# xmega32devboard.net
KiCad netlist of a schematic drawn in EAGLE
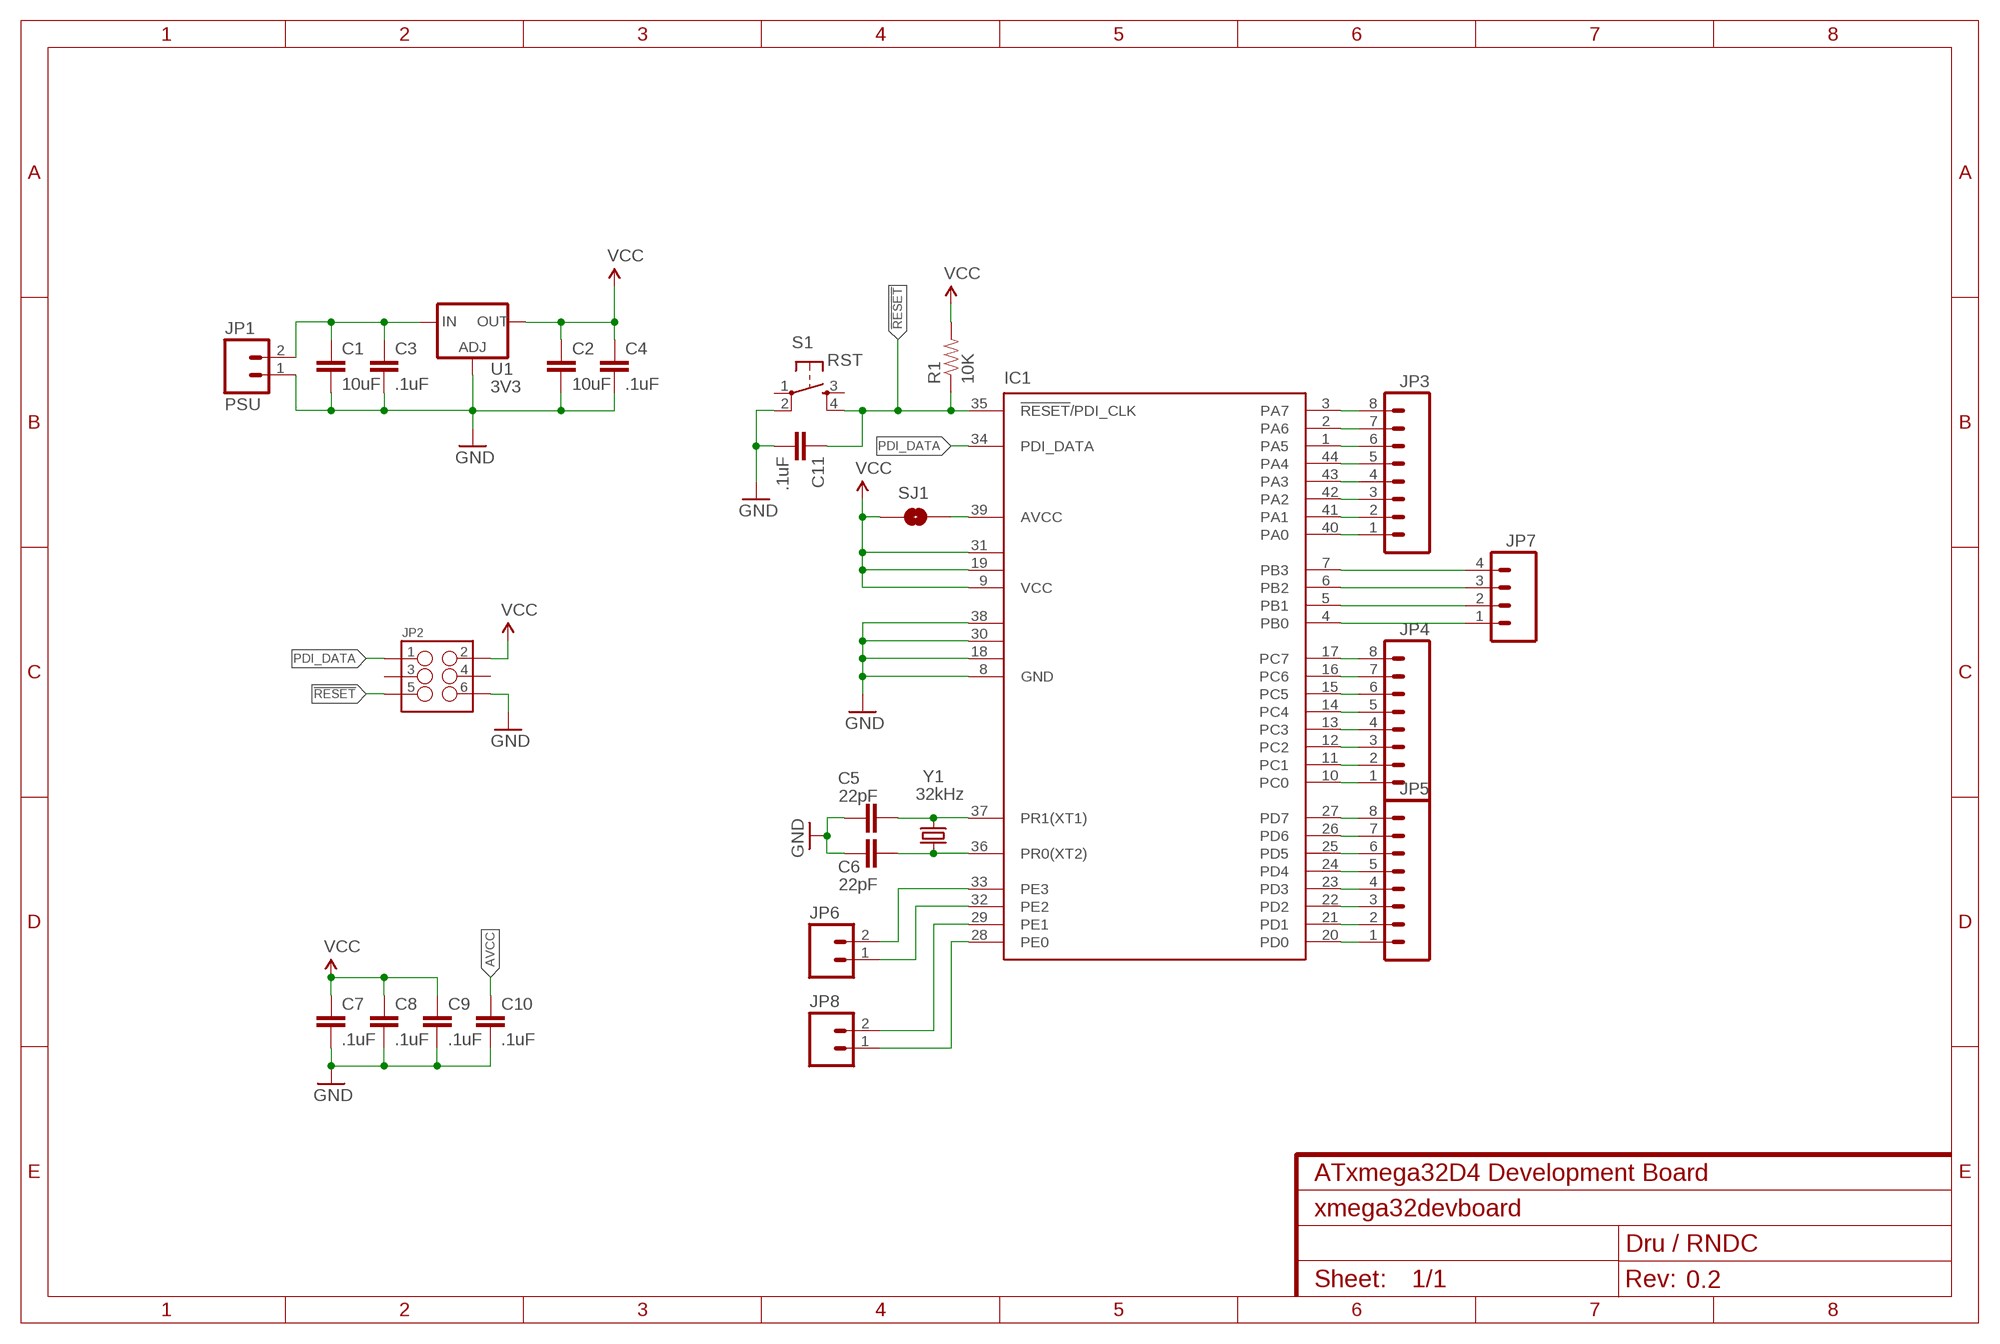
[diagram p0: schematic, sheet 1]

(export (version "E")
  (design (tool "Eeschema 10.0.6"))
  (components
    (comp (ref "C1")
      (value "10uF")
      (footprint "eagle-import:0603-CAP")
      (libsource (lib "eagle-import") (part "CAP0603-CAP"))
    )
    (comp (ref "C2")
      (value "10uF")
      (footprint "eagle-import:0603-CAP")
      (libsource (lib "eagle-import") (part "CAP0603-CAP"))
    )
    (comp (ref "C3")
      (value ".1uF")
      (footprint "eagle-import:0805")
      (libsource (lib "eagle-import") (part "CAP0805"))
    )
    (comp (ref "C4")
      (value ".1uF")
      (footprint "eagle-import:0805")
      (libsource (lib "eagle-import") (part "CAP0805"))
    )
    (comp (ref "C5")
      (value "22pF")
      (footprint "eagle-import:0805")
      (libsource (lib "eagle-import") (part "SparkFun-Passives_CAP0805"))
    )
    (comp (ref "C6")
      (value "22pF")
      (footprint "eagle-import:0805")
      (libsource (lib "eagle-import") (part "SparkFun-Passives_CAP0805"))
    )
    (comp (ref "C7")
      (value ".1uF")
      (footprint "eagle-import:0805")
      (libsource (lib "eagle-import") (part "CAP0805"))
    )
    (comp (ref "C8")
      (value ".1uF")
      (footprint "eagle-import:0805")
      (libsource (lib "eagle-import") (part "CAP0805"))
    )
    (comp (ref "C9")
      (value ".1uF")
      (footprint "eagle-import:0805")
      (libsource (lib "eagle-import") (part "CAP0805"))
    )
    (comp (ref "C10")
      (value ".1uF")
      (footprint "eagle-import:0805")
      (libsource (lib "eagle-import") (part "CAP0805"))
    )
    (comp (ref "C11")
      (value ".1uF")
      (footprint "eagle-import:0805")
      (libsource (lib "eagle-import") (part "CAP0805"))
    )
    (comp (ref "IC1")
      (value "XMEGA16A4A")
      (footprint "eagle-import:TQFP44")
      (libsource (lib "eagle-import") (part "XMEGA16A4A"))
    )
    (comp (ref "JP1")
      (value "PSU")
      (footprint "eagle-import:1X02")
      (libsource (lib "eagle-import") (part "M02PTH"))
    )
    (comp (ref "JP2")
      (value "M03X2NO_SILK")
      (footprint "eagle-import:2X3-NS")
      (libsource (lib "eagle-import") (part "M03X2NO_SILK"))
    )
    (comp (ref "JP3")
      (value "M081X08")
      (footprint "eagle-import:1X08")
      (libsource (lib "eagle-import") (part "M081X08"))
    )
    (comp (ref "JP4")
      (value "M081X08")
      (footprint "eagle-import:1X08")
      (libsource (lib "eagle-import") (part "M081X08"))
    )
    (comp (ref "JP5")
      (value "M081X08")
      (footprint "eagle-import:1X08")
      (libsource (lib "eagle-import") (part "M081X08"))
    )
    (comp (ref "JP6")
      (value "M02PTH")
      (footprint "eagle-import:1X02")
      (libsource (lib "eagle-import") (part "M02PTH"))
    )
    (comp (ref "JP7")
      (value "M04PTH")
      (footprint "eagle-import:1X04")
      (libsource (lib "eagle-import") (part "M04PTH"))
    )
    (comp (ref "JP8")
      (value "M02PTH")
      (footprint "eagle-import:1X02")
      (libsource (lib "eagle-import") (part "M02PTH"))
    )
    (comp (ref "R1")
      (value "10K")
      (footprint "eagle-import:0603-RES")
      (libsource (lib "eagle-import") (part "RESISTOR0603-RES"))
    )
    (comp (ref "S1")
      (value "RST")
      (footprint "eagle-import:TACTILE-SWITCH-SMD")
      (libsource (lib "eagle-import") (part "TAC_SWITCHSMD"))
    )
    (comp (ref "SJ1")
      (value "JUMPER-PAD-2-NO")
      (footprint "eagle-import:PAD-JUMPER-2-NO_NO_SILK")
      (libsource (lib "eagle-import") (part "JUMPER-PAD-2-NO"))
    )
    (comp (ref "U1")
      (value "3V3")
      (footprint "eagle-import:SOT223")
      (libsource (lib "eagle-import") (part "V_REG_317SMD"))
    )
    (comp (ref "Y1")
      (value "32kHz")
      (footprint "eagle-import:TC38H")
      (libsource (lib "eagle-import") (part "CRYSTALTC38H"))
    )
  )
  (nets
    (net (code "1") (name "/~{RESET}") (class "Default")
      (node (ref "C11") (pin "1") (pinfunction "1_1") (pintype "passive"))
      (node (ref "IC1") (pin "35") (pinfunction "~{RESET}/PDI_CLK_35") (pintype "bidirectional"))
      (node (ref "JP2") (pin "5") (pinfunction "5_5") (pintype "bidirectional"))
      (node (ref "R1") (pin "1") (pinfunction "1_1") (pintype "passive"))
      (node (ref "S1") (pin "4") (pinfunction "4_4") (pintype "passive"))
    )
    (net (code "2") (name "AVCC") (class "Default")
      (node (ref "C10") (pin "1") (pinfunction "1_1") (pintype "passive"))
      (node (ref "IC1") (pin "39") (pinfunction "AVCC_39") (pintype "power_in"))
      (node (ref "SJ1") (pin "2") (pinfunction "2_2") (pintype "passive"))
    )
    (net (code "3") (name "GND") (class "Default")
      (node (ref "C1") (pin "2") (pinfunction "2_2") (pintype "passive"))
      (node (ref "C10") (pin "2") (pinfunction "2_2") (pintype "passive"))
      (node (ref "C11") (pin "2") (pinfunction "2_2") (pintype "passive"))
      (node (ref "C2") (pin "2") (pinfunction "2_2") (pintype "passive"))
      (node (ref "C3") (pin "2") (pinfunction "2_2") (pintype "passive"))
      (node (ref "C4") (pin "2") (pinfunction "2_2") (pintype "passive"))
      (node (ref "C5") (pin "1") (pinfunction "1_1") (pintype "passive"))
      (node (ref "C6") (pin "1") (pinfunction "1_1") (pintype "passive"))
      (node (ref "C7") (pin "2") (pinfunction "2_2") (pintype "passive"))
      (node (ref "C8") (pin "2") (pinfunction "2_2") (pintype "passive"))
      (node (ref "C9") (pin "2") (pinfunction "2_2") (pintype "passive"))
      (node (ref "IC1") (pin "18") (pinfunction "GND1_18") (pintype "power_in"))
      (node (ref "IC1") (pin "30") (pinfunction "GND2_30") (pintype "power_in"))
      (node (ref "IC1") (pin "38") (pinfunction "GND3_38") (pintype "power_in"))
      (node (ref "IC1") (pin "8") (pinfunction "GND_8") (pintype "power_in"))
      (node (ref "JP1") (pin "1") (pinfunction "1_1") (pintype "passive"))
      (node (ref "JP2") (pin "6") (pinfunction "6_6") (pintype "bidirectional"))
      (node (ref "S1") (pin "2") (pinfunction "2_2") (pintype "passive"))
      (node (ref "U1") (pin "1") (pinfunction "ADJ_1") (pintype "input"))
    )
    (net (code "4") (name "Net-(IC1-PA0)") (class "Default")
      (node (ref "IC1") (pin "40") (pinfunction "PA0_40") (pintype "bidirectional"))
      (node (ref "JP3") (pin "1") (pinfunction "1_1") (pintype "passive"))
    )
    (net (code "5") (name "Net-(IC1-PA1)") (class "Default")
      (node (ref "IC1") (pin "41") (pinfunction "PA1_41") (pintype "bidirectional"))
      (node (ref "JP3") (pin "2") (pinfunction "2_2") (pintype "passive"))
    )
    (net (code "6") (name "Net-(IC1-PA2)") (class "Default")
      (node (ref "IC1") (pin "42") (pinfunction "PA2_42") (pintype "bidirectional"))
      (node (ref "JP3") (pin "3") (pinfunction "3_3") (pintype "passive"))
    )
    (net (code "7") (name "Net-(IC1-PA3)") (class "Default")
      (node (ref "IC1") (pin "43") (pinfunction "PA3_43") (pintype "bidirectional"))
      (node (ref "JP3") (pin "4") (pinfunction "4_4") (pintype "passive"))
    )
    (net (code "8") (name "Net-(IC1-PA4)") (class "Default")
      (node (ref "IC1") (pin "44") (pinfunction "PA4_44") (pintype "bidirectional"))
      (node (ref "JP3") (pin "5") (pinfunction "5_5") (pintype "passive"))
    )
    (net (code "9") (name "Net-(IC1-PA5)") (class "Default")
      (node (ref "IC1") (pin "1") (pinfunction "PA5_1") (pintype "bidirectional"))
      (node (ref "JP3") (pin "6") (pinfunction "6_6") (pintype "passive"))
    )
    (net (code "10") (name "Net-(IC1-PA6)") (class "Default")
      (node (ref "IC1") (pin "2") (pinfunction "PA6_2") (pintype "bidirectional"))
      (node (ref "JP3") (pin "7") (pinfunction "7_7") (pintype "passive"))
    )
    (net (code "11") (name "Net-(IC1-PA7)") (class "Default")
      (node (ref "IC1") (pin "3") (pinfunction "PA7_3") (pintype "bidirectional"))
      (node (ref "JP3") (pin "8") (pinfunction "8_8") (pintype "passive"))
    )
    (net (code "12") (name "Net-(IC1-PB0)") (class "Default")
      (node (ref "IC1") (pin "4") (pinfunction "PB0_4") (pintype "bidirectional"))
      (node (ref "JP7") (pin "1") (pinfunction "1_1") (pintype "passive"))
    )
    (net (code "13") (name "Net-(IC1-PB1)") (class "Default")
      (node (ref "IC1") (pin "5") (pinfunction "PB1_5") (pintype "bidirectional"))
      (node (ref "JP7") (pin "2") (pinfunction "2_2") (pintype "passive"))
    )
    (net (code "14") (name "Net-(IC1-PB2)") (class "Default")
      (node (ref "IC1") (pin "6") (pinfunction "PB2_6") (pintype "bidirectional"))
      (node (ref "JP7") (pin "3") (pinfunction "3_3") (pintype "passive"))
    )
    (net (code "15") (name "Net-(IC1-PB3)") (class "Default")
      (node (ref "IC1") (pin "7") (pinfunction "PB3_7") (pintype "bidirectional"))
      (node (ref "JP7") (pin "4") (pinfunction "4_4") (pintype "passive"))
    )
    (net (code "16") (name "Net-(IC1-PC0)") (class "Default")
      (node (ref "IC1") (pin "10") (pinfunction "PC0_10") (pintype "bidirectional"))
      (node (ref "JP4") (pin "1") (pinfunction "1_1") (pintype "passive"))
    )
    (net (code "17") (name "Net-(IC1-PC1)") (class "Default")
      (node (ref "IC1") (pin "11") (pinfunction "PC1_11") (pintype "bidirectional"))
      (node (ref "JP4") (pin "2") (pinfunction "2_2") (pintype "passive"))
    )
    (net (code "18") (name "Net-(IC1-PC2)") (class "Default")
      (node (ref "IC1") (pin "12") (pinfunction "PC2_12") (pintype "bidirectional"))
      (node (ref "JP4") (pin "3") (pinfunction "3_3") (pintype "passive"))
    )
    (net (code "19") (name "Net-(IC1-PC3)") (class "Default")
      (node (ref "IC1") (pin "13") (pinfunction "PC3_13") (pintype "bidirectional"))
      (node (ref "JP4") (pin "4") (pinfunction "4_4") (pintype "passive"))
    )
    (net (code "20") (name "Net-(IC1-PC4)") (class "Default")
      (node (ref "IC1") (pin "14") (pinfunction "PC4_14") (pintype "bidirectional"))
      (node (ref "JP4") (pin "5") (pinfunction "5_5") (pintype "passive"))
    )
    (net (code "21") (name "Net-(IC1-PC5)") (class "Default")
      (node (ref "IC1") (pin "15") (pinfunction "PC5_15") (pintype "bidirectional"))
      (node (ref "JP4") (pin "6") (pinfunction "6_6") (pintype "passive"))
    )
    (net (code "22") (name "Net-(IC1-PC6)") (class "Default")
      (node (ref "IC1") (pin "16") (pinfunction "PC6_16") (pintype "bidirectional"))
      (node (ref "JP4") (pin "7") (pinfunction "7_7") (pintype "passive"))
    )
    (net (code "23") (name "Net-(IC1-PC7)") (class "Default")
      (node (ref "IC1") (pin "17") (pinfunction "PC7_17") (pintype "bidirectional"))
      (node (ref "JP4") (pin "8") (pinfunction "8_8") (pintype "passive"))
    )
    (net (code "24") (name "Net-(IC1-PD0)") (class "Default")
      (node (ref "IC1") (pin "20") (pinfunction "PD0_20") (pintype "bidirectional"))
      (node (ref "JP5") (pin "1") (pinfunction "1_1") (pintype "passive"))
    )
    (net (code "25") (name "Net-(IC1-PD1)") (class "Default")
      (node (ref "IC1") (pin "21") (pinfunction "PD1_21") (pintype "bidirectional"))
      (node (ref "JP5") (pin "2") (pinfunction "2_2") (pintype "passive"))
    )
    (net (code "26") (name "Net-(IC1-PD2)") (class "Default")
      (node (ref "IC1") (pin "22") (pinfunction "PD2_22") (pintype "bidirectional"))
      (node (ref "JP5") (pin "3") (pinfunction "3_3") (pintype "passive"))
    )
    (net (code "27") (name "Net-(IC1-PD3)") (class "Default")
      (node (ref "IC1") (pin "23") (pinfunction "PD3_23") (pintype "bidirectional"))
      (node (ref "JP5") (pin "4") (pinfunction "4_4") (pintype "passive"))
    )
    (net (code "28") (name "Net-(IC1-PD4)") (class "Default")
      (node (ref "IC1") (pin "24") (pinfunction "PD4_24") (pintype "bidirectional"))
      (node (ref "JP5") (pin "5") (pinfunction "5_5") (pintype "passive"))
    )
    (net (code "29") (name "Net-(IC1-PD5)") (class "Default")
      (node (ref "IC1") (pin "25") (pinfunction "PD5_25") (pintype "bidirectional"))
      (node (ref "JP5") (pin "6") (pinfunction "6_6") (pintype "passive"))
    )
    (net (code "30") (name "Net-(IC1-PD6)") (class "Default")
      (node (ref "IC1") (pin "26") (pinfunction "PD6_26") (pintype "bidirectional"))
      (node (ref "JP5") (pin "7") (pinfunction "7_7") (pintype "passive"))
    )
    (net (code "31") (name "Net-(IC1-PD7)") (class "Default")
      (node (ref "IC1") (pin "27") (pinfunction "PD7_27") (pintype "bidirectional"))
      (node (ref "JP5") (pin "8") (pinfunction "8_8") (pintype "passive"))
    )
    (net (code "32") (name "Net-(IC1-PE0)") (class "Default")
      (node (ref "IC1") (pin "28") (pinfunction "PE0_28") (pintype "bidirectional"))
      (node (ref "JP8") (pin "1") (pinfunction "1_1") (pintype "passive"))
    )
    (net (code "33") (name "Net-(IC1-PE1)") (class "Default")
      (node (ref "IC1") (pin "29") (pinfunction "PE1_29") (pintype "bidirectional"))
      (node (ref "JP8") (pin "2") (pinfunction "2_2") (pintype "passive"))
    )
    (net (code "34") (name "Net-(IC1-PE2)") (class "Default")
      (node (ref "IC1") (pin "32") (pinfunction "PE2_32") (pintype "bidirectional"))
      (node (ref "JP6") (pin "1") (pinfunction "1_1") (pintype "passive"))
    )
    (net (code "35") (name "Net-(IC1-PE3)") (class "Default")
      (node (ref "IC1") (pin "33") (pinfunction "PE3_33") (pintype "bidirectional"))
      (node (ref "JP6") (pin "2") (pinfunction "2_2") (pintype "passive"))
    )
    (net (code "36") (name "Net-(IC1-PR0(XT2))") (class "Default")
      (node (ref "C6") (pin "2") (pinfunction "2_2") (pintype "passive"))
      (node (ref "IC1") (pin "36") (pinfunction "PR0(XT2)_36") (pintype "bidirectional"))
      (node (ref "Y1") (pin "2") (pinfunction "2_2") (pintype "passive"))
    )
    (net (code "37") (name "Net-(IC1-PR1(XT1))") (class "Default")
      (node (ref "C5") (pin "2") (pinfunction "2_2") (pintype "passive"))
      (node (ref "IC1") (pin "37") (pinfunction "PR1(XT1)_37") (pintype "bidirectional"))
      (node (ref "Y1") (pin "1") (pinfunction "1_1") (pintype "passive"))
    )
    (net (code "38") (name "Net-(U1-IN)") (class "Default")
      (node (ref "C1") (pin "1") (pinfunction "1_1") (pintype "passive"))
      (node (ref "C3") (pin "1") (pinfunction "1_1") (pintype "passive"))
      (node (ref "JP1") (pin "2") (pinfunction "2_2") (pintype "passive"))
      (node (ref "U1") (pin "3") (pinfunction "IN_3") (pintype "input"))
    )
    (net (code "39") (name "PDI_DATA") (class "Default")
      (node (ref "IC1") (pin "34") (pinfunction "PDI_DATA_34") (pintype "bidirectional"))
      (node (ref "JP2") (pin "1") (pinfunction "1_1") (pintype "bidirectional"))
    )
    (net (code "40") (name "VCC") (class "Default")
      (node (ref "C2") (pin "1") (pinfunction "1_1") (pintype "passive"))
      (node (ref "C4") (pin "1") (pinfunction "1_1") (pintype "passive"))
      (node (ref "C7") (pin "1") (pinfunction "1_1") (pintype "passive"))
      (node (ref "C8") (pin "1") (pinfunction "1_1") (pintype "passive"))
      (node (ref "C9") (pin "1") (pinfunction "1_1") (pintype "passive"))
      (node (ref "IC1") (pin "19") (pinfunction "VCC1_19") (pintype "power_in"))
      (node (ref "IC1") (pin "31") (pinfunction "VCC2_31") (pintype "power_in"))
      (node (ref "IC1") (pin "9") (pinfunction "VCC_9") (pintype "power_in"))
      (node (ref "JP2") (pin "2") (pinfunction "2_2") (pintype "bidirectional"))
      (node (ref "R1") (pin "2") (pinfunction "2_2") (pintype "passive"))
      (node (ref "SJ1") (pin "1") (pinfunction "1_1") (pintype "passive"))
      (node (ref "U1") (pin "2") (pinfunction "OUT_2") (pintype "output"))
    )
    (net (code "41") (name "unconnected-(JP2-Pad3)") (class "Default")
      (node (ref "JP2") (pin "3") (pinfunction "3_3") (pintype "bidirectional"))
    )
    (net (code "42") (name "unconnected-(JP2-Pad4)") (class "Default")
      (node (ref "JP2") (pin "4") (pinfunction "4_4") (pintype "bidirectional"))
    )
    (net (code "43") (name "unconnected-(S1-Pad1)") (class "Default")
      (node (ref "S1") (pin "1") (pinfunction "1_1") (pintype "passive"))
    )
    (net (code "44") (name "unconnected-(S1-Pad3)") (class "Default")
      (node (ref "S1") (pin "3") (pinfunction "3_3") (pintype "passive"))
    )
  )
)
